# Quest.net
KiCad netlist of a schematic drawn in EAGLE
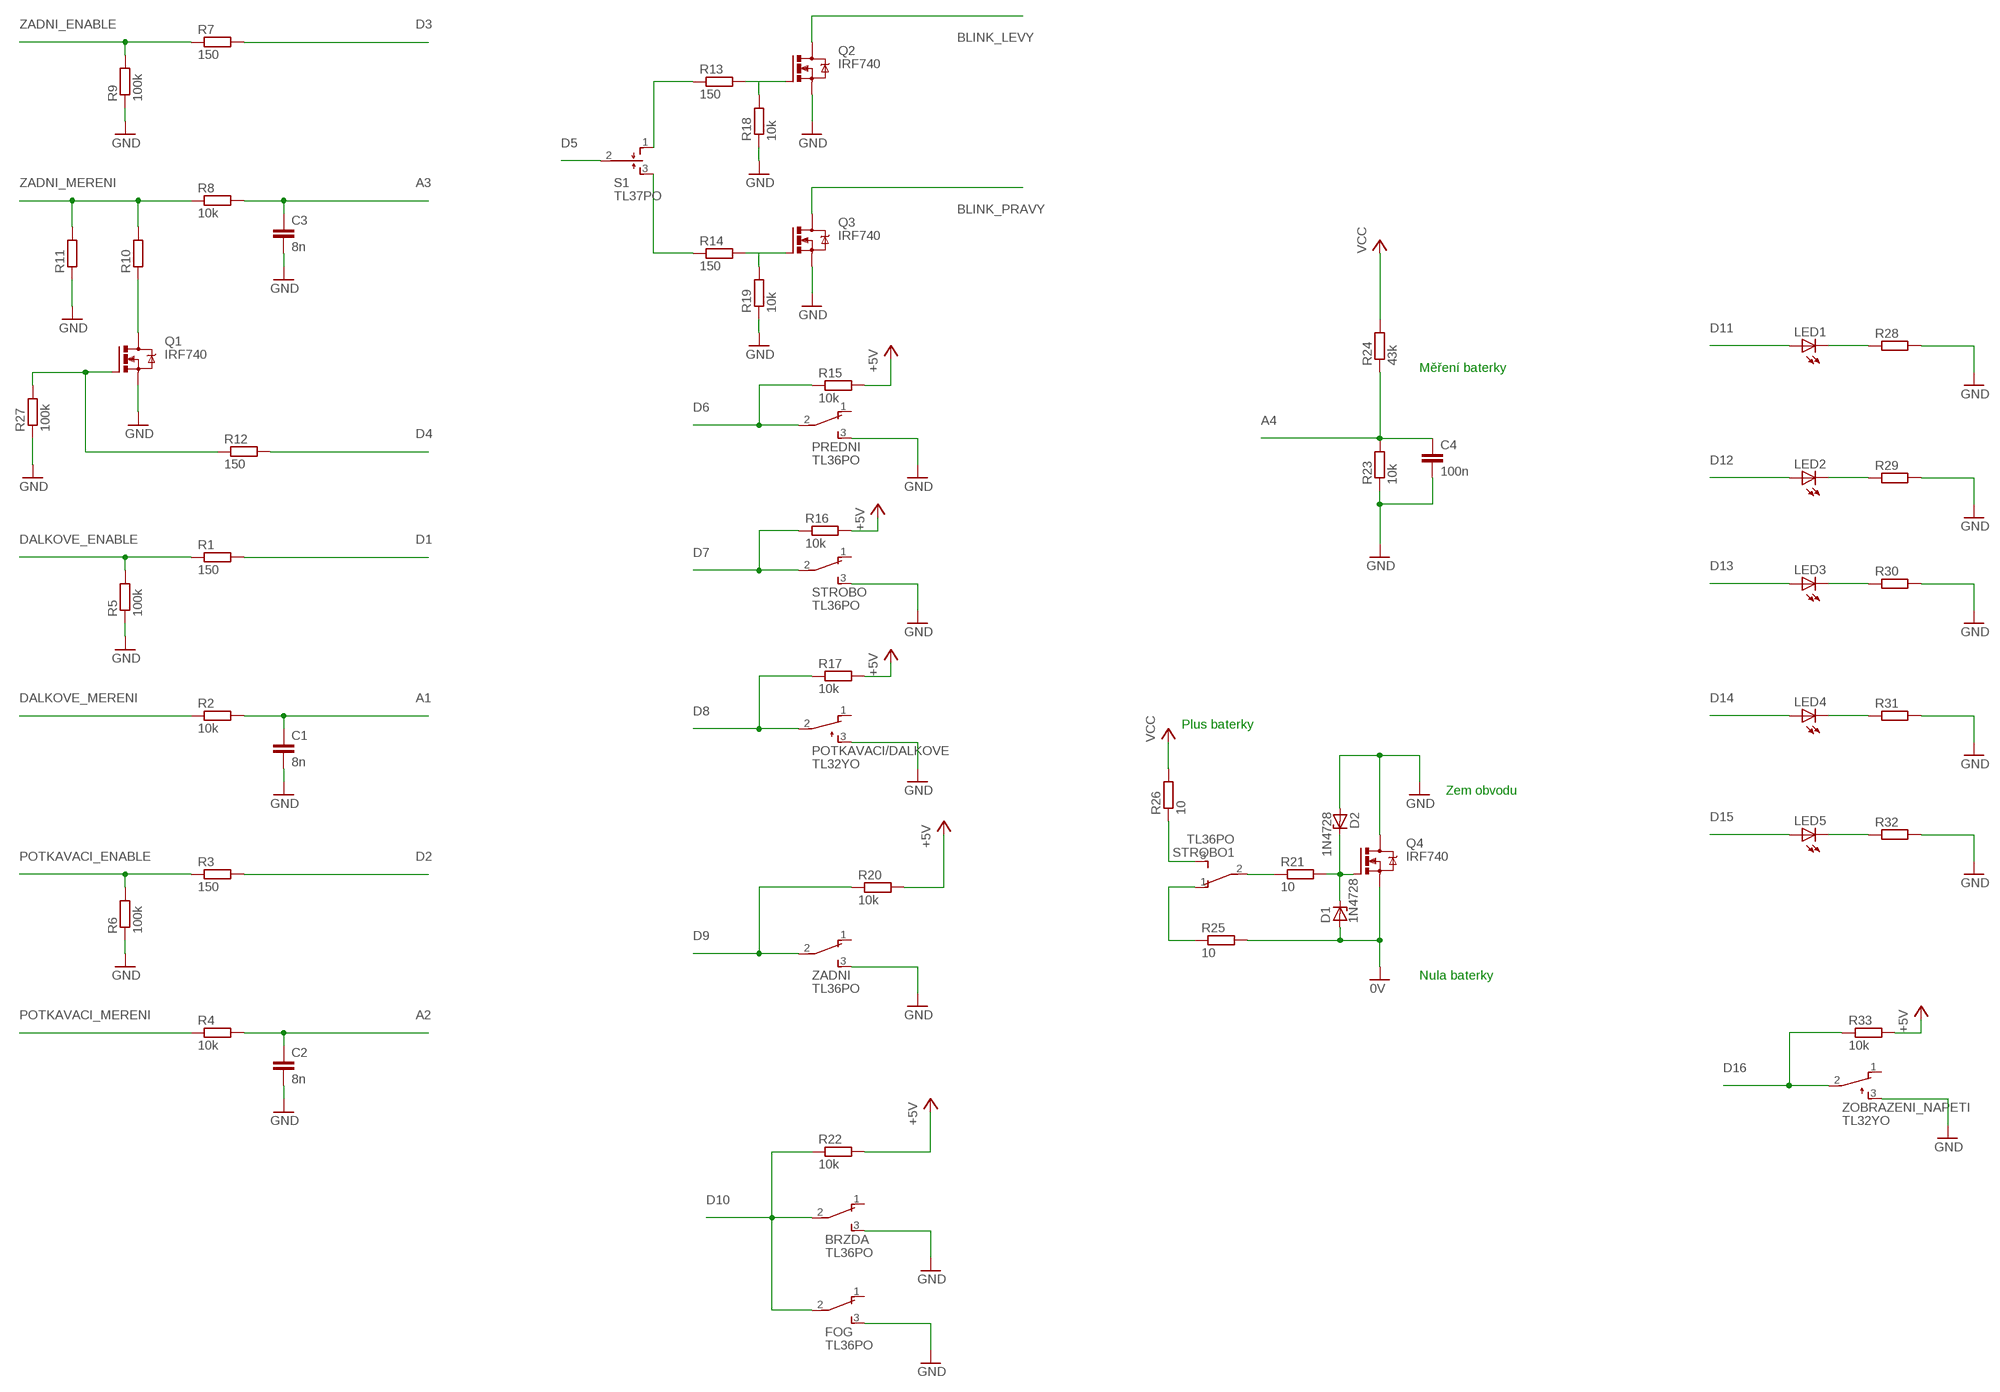
[diagram p0: schematic, sheet 1]

(export (version "E")
  (design (tool "Eeschema 10.0.6"))
  (components
    (comp (ref "BRZDA")
      (value "TL36PO")
      (footprint "eagle-import:TL3XPO")
      (libsource (lib "eagle-import") (part "TL36PO"))
    )
    (comp (ref "C1")
      (value "8n")
      (footprint "eagle-import:C050-024X044")
      (libsource (lib "eagle-import") (part "C-EU050-024X044"))
    )
    (comp (ref "C2")
      (value "8n")
      (footprint "eagle-import:C050-024X044")
      (libsource (lib "eagle-import") (part "C-EU050-024X044"))
    )
    (comp (ref "C3")
      (value "8n")
      (footprint "eagle-import:C050-024X044")
      (libsource (lib "eagle-import") (part "C-EU050-024X044"))
    )
    (comp (ref "C4")
      (value "100n")
      (footprint "eagle-import:C050-024X044")
      (libsource (lib "eagle-import") (part "C-EU050-024X044"))
    )
    (comp (ref "D1")
      (value "1N4728")
      (footprint "eagle-import:DO41Z10")
      (libsource (lib "eagle-import") (part "1N4728"))
    )
    (comp (ref "D2")
      (value "1N4728")
      (footprint "eagle-import:DO41Z10")
      (libsource (lib "eagle-import") (part "1N4728"))
    )
    (comp (ref "FOG")
      (value "TL36PO")
      (footprint "eagle-import:TL3XPO")
      (libsource (lib "eagle-import") (part "TL36PO"))
    )
    (comp (ref "LED1")
      (value "LED5MM")
      (footprint "eagle-import:LED5MM")
      (libsource (lib "eagle-import") (part "LED5MM"))
    )
    (comp (ref "LED2")
      (value "LED5MM")
      (footprint "eagle-import:LED5MM")
      (libsource (lib "eagle-import") (part "LED5MM"))
    )
    (comp (ref "LED3")
      (value "LED5MM")
      (footprint "eagle-import:LED5MM")
      (libsource (lib "eagle-import") (part "LED5MM"))
    )
    (comp (ref "LED4")
      (value "LED5MM")
      (footprint "eagle-import:LED5MM")
      (libsource (lib "eagle-import") (part "LED5MM"))
    )
    (comp (ref "LED5")
      (value "LED5MM")
      (footprint "eagle-import:LED5MM")
      (libsource (lib "eagle-import") (part "LED5MM"))
    )
    (comp (ref "POTKAVACI/DALKOVE")
      (value "TL32YO")
      (footprint "eagle-import:TL3XYO")
      (libsource (lib "eagle-import") (part "TL32YO"))
    )
    (comp (ref "PREDNI")
      (value "TL36PO")
      (footprint "eagle-import:TL3XPO")
      (libsource (lib "eagle-import") (part "TL36PO"))
    )
    (comp (ref "Q1")
      (value "IRF740")
      (footprint "eagle-import:TO220BV")
      (libsource (lib "eagle-import") (part "IRF740"))
    )
    (comp (ref "Q2")
      (value "IRF740")
      (footprint "eagle-import:TO220BV")
      (libsource (lib "eagle-import") (part "IRF740"))
    )
    (comp (ref "Q3")
      (value "IRF740")
      (footprint "eagle-import:TO220BV")
      (libsource (lib "eagle-import") (part "IRF740"))
    )
    (comp (ref "Q4")
      (value "IRF740")
      (footprint "eagle-import:TO220BV")
      (libsource (lib "eagle-import") (part "IRF740"))
    )
    (comp (ref "R1")
      (value "150")
      (footprint "eagle-import:0309_10")
      (libsource (lib "eagle-import") (part "R-EU_0309/10"))
    )
    (comp (ref "R2")
      (value "10k")
      (footprint "eagle-import:0309_10")
      (libsource (lib "eagle-import") (part "R-EU_0309/10"))
    )
    (comp (ref "R3")
      (value "150")
      (footprint "eagle-import:0309_10")
      (libsource (lib "eagle-import") (part "R-EU_0309/10"))
    )
    (comp (ref "R4")
      (value "10k")
      (footprint "eagle-import:0309_10")
      (libsource (lib "eagle-import") (part "R-EU_0309/10"))
    )
    (comp (ref "R5")
      (value "100k")
      (footprint "eagle-import:0309_10")
      (libsource (lib "eagle-import") (part "R-EU_0309/10"))
    )
    (comp (ref "R6")
      (value "100k")
      (footprint "eagle-import:0309_10")
      (libsource (lib "eagle-import") (part "R-EU_0309/10"))
    )
    (comp (ref "R7")
      (value "150")
      (footprint "eagle-import:0309_10")
      (libsource (lib "eagle-import") (part "R-EU_0309/10"))
    )
    (comp (ref "R8")
      (value "10k")
      (footprint "eagle-import:0309_10")
      (libsource (lib "eagle-import") (part "R-EU_0309/10"))
    )
    (comp (ref "R9")
      (value "100k")
      (footprint "eagle-import:0309_10")
      (libsource (lib "eagle-import") (part "R-EU_0309/10"))
    )
    (comp (ref "R10")
      (value "R-EU_0309/10")
      (footprint "eagle-import:0309_10")
      (libsource (lib "eagle-import") (part "R-EU_0309/10"))
    )
    (comp (ref "R11")
      (value "R-EU_0309/10")
      (footprint "eagle-import:0309_10")
      (libsource (lib "eagle-import") (part "R-EU_0309/10"))
    )
    (comp (ref "R12")
      (value "150")
      (footprint "eagle-import:0309_10")
      (libsource (lib "eagle-import") (part "R-EU_0309/10"))
    )
    (comp (ref "R13")
      (value "150")
      (footprint "eagle-import:0309_10")
      (libsource (lib "eagle-import") (part "R-EU_0309/10"))
    )
    (comp (ref "R14")
      (value "150")
      (footprint "eagle-import:0309_10")
      (libsource (lib "eagle-import") (part "R-EU_0309/10"))
    )
    (comp (ref "R15")
      (value "10k")
      (footprint "eagle-import:0309_10")
      (libsource (lib "eagle-import") (part "R-EU_0309/10"))
    )
    (comp (ref "R16")
      (value "10k")
      (footprint "eagle-import:0309_10")
      (libsource (lib "eagle-import") (part "R-EU_0309/10"))
    )
    (comp (ref "R17")
      (value "10k")
      (footprint "eagle-import:0309_10")
      (libsource (lib "eagle-import") (part "R-EU_0309/10"))
    )
    (comp (ref "R18")
      (value "10k")
      (footprint "eagle-import:0309_10")
      (libsource (lib "eagle-import") (part "R-EU_0309/10"))
    )
    (comp (ref "R19")
      (value "10k")
      (footprint "eagle-import:0309_10")
      (libsource (lib "eagle-import") (part "R-EU_0309/10"))
    )
    (comp (ref "R20")
      (value "10k")
      (footprint "eagle-import:0309_10")
      (libsource (lib "eagle-import") (part "R-EU_0309/10"))
    )
    (comp (ref "R21")
      (value "10")
      (footprint "eagle-import:0309_10")
      (libsource (lib "eagle-import") (part "R-EU_0309/10"))
    )
    (comp (ref "R22")
      (value "10k")
      (footprint "eagle-import:0309_10")
      (libsource (lib "eagle-import") (part "R-EU_0309/10"))
    )
    (comp (ref "R23")
      (value "10k")
      (footprint "eagle-import:0309_10")
      (libsource (lib "eagle-import") (part "R-EU_0309/10"))
    )
    (comp (ref "R24")
      (value "43k")
      (footprint "eagle-import:0309_10")
      (libsource (lib "eagle-import") (part "R-EU_0309/10"))
    )
    (comp (ref "R25")
      (value "10")
      (footprint "eagle-import:0309_10")
      (libsource (lib "eagle-import") (part "R-EU_0309/10"))
    )
    (comp (ref "R26")
      (value "10")
      (footprint "eagle-import:0309_10")
      (libsource (lib "eagle-import") (part "R-EU_0309/10"))
    )
    (comp (ref "R27")
      (value "100k")
      (footprint "eagle-import:0309_10")
      (libsource (lib "eagle-import") (part "R-EU_0309/10"))
    )
    (comp (ref "R28")
      (value "R-EU_0309/10")
      (footprint "eagle-import:0309_10")
      (libsource (lib "eagle-import") (part "R-EU_0309/10"))
    )
    (comp (ref "R29")
      (value "R-EU_0309/10")
      (footprint "eagle-import:0309_10")
      (libsource (lib "eagle-import") (part "R-EU_0309/10"))
    )
    (comp (ref "R30")
      (value "R-EU_0309/10")
      (footprint "eagle-import:0309_10")
      (libsource (lib "eagle-import") (part "R-EU_0309/10"))
    )
    (comp (ref "R31")
      (value "R-EU_0309/10")
      (footprint "eagle-import:0309_10")
      (libsource (lib "eagle-import") (part "R-EU_0309/10"))
    )
    (comp (ref "R32")
      (value "R-EU_0309/10")
      (footprint "eagle-import:0309_10")
      (libsource (lib "eagle-import") (part "R-EU_0309/10"))
    )
    (comp (ref "R33")
      (value "10k")
      (footprint "eagle-import:0309_10")
      (libsource (lib "eagle-import") (part "R-EU_0309/10"))
    )
    (comp (ref "S1")
      (value "TL37PO")
      (footprint "eagle-import:TL3XPO")
      (libsource (lib "eagle-import") (part "TL37PO"))
    )
    (comp (ref "STROBO")
      (value "TL36PO")
      (footprint "eagle-import:TL3XPO")
      (libsource (lib "eagle-import") (part "TL36PO"))
    )
    (comp (ref "STROBO1")
      (value "TL36PO")
      (footprint "eagle-import:TL3XPO")
      (libsource (lib "eagle-import") (part "TL36PO"))
    )
    (comp (ref "ZADNI")
      (value "TL36PO")
      (footprint "eagle-import:TL3XPO")
      (libsource (lib "eagle-import") (part "TL36PO"))
    )
    (comp (ref "ZOBRAZENI_NAPETI")
      (value "TL32YO")
      (footprint "eagle-import:TL3XYO")
      (libsource (lib "eagle-import") (part "TL32YO"))
    )
  )
  (nets
    (net (code "1") (name "+5V") (class "Default")
      (node (ref "R15") (pin "2") (pinfunction "2_2") (pintype "passive"))
      (node (ref "R16") (pin "2") (pinfunction "2_2") (pintype "passive"))
      (node (ref "R17") (pin "2") (pinfunction "2_2") (pintype "passive"))
      (node (ref "R20") (pin "2") (pinfunction "2_2") (pintype "passive"))
      (node (ref "R22") (pin "2") (pinfunction "2_2") (pintype "passive"))
      (node (ref "R33") (pin "2") (pinfunction "2_2") (pintype "passive"))
    )
    (net (code "2") (name "/A1") (class "Default")
      (node (ref "C1") (pin "1") (pinfunction "1_1") (pintype "passive"))
      (node (ref "R2") (pin "2") (pinfunction "2_2") (pintype "passive"))
    )
    (net (code "3") (name "/A2") (class "Default")
      (node (ref "C2") (pin "1") (pinfunction "1_1") (pintype "passive"))
      (node (ref "R4") (pin "2") (pinfunction "2_2") (pintype "passive"))
    )
    (net (code "4") (name "/A3") (class "Default")
      (node (ref "C3") (pin "1") (pinfunction "1_1") (pintype "passive"))
      (node (ref "R8") (pin "2") (pinfunction "2_2") (pintype "passive"))
    )
    (net (code "5") (name "/A4") (class "Default")
      (node (ref "C4") (pin "1") (pinfunction "1_1") (pintype "passive"))
      (node (ref "R23") (pin "2") (pinfunction "2_2") (pintype "passive"))
      (node (ref "R24") (pin "1") (pinfunction "1_1") (pintype "passive"))
    )
    (net (code "6") (name "/BLINK_LEVY") (class "Default")
      (node (ref "Q2") (pin "D") (pinfunction "D_D") (pintype "passive"))
    )
    (net (code "7") (name "/BLINK_PRAVY") (class "Default")
      (node (ref "Q3") (pin "D") (pinfunction "D_D") (pintype "passive"))
    )
    (net (code "8") (name "/D1") (class "Default")
      (node (ref "R1") (pin "2") (pinfunction "2_2") (pintype "passive"))
    )
    (net (code "9") (name "/D2") (class "Default")
      (node (ref "R3") (pin "2") (pinfunction "2_2") (pintype "passive"))
    )
    (net (code "10") (name "/D3") (class "Default")
      (node (ref "R7") (pin "2") (pinfunction "2_2") (pintype "passive"))
    )
    (net (code "11") (name "/D4") (class "Default")
      (node (ref "R12") (pin "2") (pinfunction "2_2") (pintype "passive"))
    )
    (net (code "12") (name "/D5") (class "Default")
      (node (ref "S1") (pin "2") (pinfunction "P_2") (pintype "passive"))
    )
    (net (code "13") (name "/D6") (class "Default")
      (node (ref "PREDNI") (pin "2") (pinfunction "P_2") (pintype "passive"))
      (node (ref "R15") (pin "1") (pinfunction "1_1") (pintype "passive"))
    )
    (net (code "14") (name "/D7") (class "Default")
      (node (ref "R16") (pin "1") (pinfunction "1_1") (pintype "passive"))
      (node (ref "STROBO") (pin "2") (pinfunction "P_2") (pintype "passive"))
    )
    (net (code "15") (name "/D8") (class "Default")
      (node (ref "POTKAVACI/DALKOVE") (pin "2") (pinfunction "P_2") (pintype "passive"))
      (node (ref "R17") (pin "1") (pinfunction "1_1") (pintype "passive"))
    )
    (net (code "16") (name "/D9") (class "Default")
      (node (ref "R20") (pin "1") (pinfunction "1_1") (pintype "passive"))
      (node (ref "ZADNI") (pin "2") (pinfunction "P_2") (pintype "passive"))
    )
    (net (code "17") (name "/D10") (class "Default")
      (node (ref "BRZDA") (pin "2") (pinfunction "P_2") (pintype "passive"))
      (node (ref "FOG") (pin "2") (pinfunction "P_2") (pintype "passive"))
      (node (ref "R22") (pin "1") (pinfunction "1_1") (pintype "passive"))
    )
    (net (code "18") (name "/D11") (class "Default")
      (node (ref "LED1") (pin "A") (pinfunction "A_A") (pintype "passive"))
    )
    (net (code "19") (name "/D12") (class "Default")
      (node (ref "LED2") (pin "A") (pinfunction "A_A") (pintype "passive"))
    )
    (net (code "20") (name "/D13") (class "Default")
      (node (ref "LED3") (pin "A") (pinfunction "A_A") (pintype "passive"))
    )
    (net (code "21") (name "/D14") (class "Default")
      (node (ref "LED4") (pin "A") (pinfunction "A_A") (pintype "passive"))
    )
    (net (code "22") (name "/D15") (class "Default")
      (node (ref "LED5") (pin "A") (pinfunction "A_A") (pintype "passive"))
    )
    (net (code "23") (name "/D16") (class "Default")
      (node (ref "R33") (pin "1") (pinfunction "1_1") (pintype "passive"))
      (node (ref "ZOBRAZENI_NAPETI") (pin "2") (pinfunction "P_2") (pintype "passive"))
    )
    (net (code "24") (name "/DALKOVE_ENABLE") (class "Default")
      (node (ref "R1") (pin "1") (pinfunction "1_1") (pintype "passive"))
      (node (ref "R5") (pin "2") (pinfunction "2_2") (pintype "passive"))
    )
    (net (code "25") (name "/DALKOVE_MERENI") (class "Default")
      (node (ref "R2") (pin "1") (pinfunction "1_1") (pintype "passive"))
    )
    (net (code "26") (name "/POTKAVACI_ENABLE") (class "Default")
      (node (ref "R3") (pin "1") (pinfunction "1_1") (pintype "passive"))
      (node (ref "R6") (pin "2") (pinfunction "2_2") (pintype "passive"))
    )
    (net (code "27") (name "/POTKAVACI_MERENI") (class "Default")
      (node (ref "R4") (pin "1") (pinfunction "1_1") (pintype "passive"))
    )
    (net (code "28") (name "/ZADNI_ENABLE") (class "Default")
      (node (ref "R7") (pin "1") (pinfunction "1_1") (pintype "passive"))
      (node (ref "R9") (pin "2") (pinfunction "2_2") (pintype "passive"))
    )
    (net (code "29") (name "/ZADNI_MERENI") (class "Default")
      (node (ref "R10") (pin "2") (pinfunction "2_2") (pintype "passive"))
      (node (ref "R11") (pin "2") (pinfunction "2_2") (pintype "passive"))
      (node (ref "R8") (pin "1") (pinfunction "1_1") (pintype "passive"))
    )
    (net (code "30") (name "0V") (class "Default")
      (node (ref "D1") (pin "A") (pinfunction "A_A") (pintype "passive"))
      (node (ref "Q4") (pin "S") (pinfunction "S_S") (pintype "passive"))
      (node (ref "R25") (pin "2") (pinfunction "2_2") (pintype "passive"))
    )
    (net (code "31") (name "GND") (class "Default")
      (node (ref "BRZDA") (pin "3") (pinfunction "S_3") (pintype "passive"))
      (node (ref "C1") (pin "2") (pinfunction "2_2") (pintype "passive"))
      (node (ref "C2") (pin "2") (pinfunction "2_2") (pintype "passive"))
      (node (ref "C3") (pin "2") (pinfunction "2_2") (pintype "passive"))
      (node (ref "C4") (pin "2") (pinfunction "2_2") (pintype "passive"))
      (node (ref "D2") (pin "A") (pinfunction "A_A") (pintype "passive"))
      (node (ref "FOG") (pin "3") (pinfunction "S_3") (pintype "passive"))
      (node (ref "POTKAVACI/DALKOVE") (pin "3") (pinfunction "S_3") (pintype "passive"))
      (node (ref "PREDNI") (pin "3") (pinfunction "S_3") (pintype "passive"))
      (node (ref "Q1") (pin "S") (pinfunction "S_S") (pintype "passive"))
      (node (ref "Q2") (pin "S") (pinfunction "S_S") (pintype "passive"))
      (node (ref "Q3") (pin "S") (pinfunction "S_S") (pintype "passive"))
      (node (ref "Q4") (pin "D") (pinfunction "D_D") (pintype "passive"))
      (node (ref "R11") (pin "1") (pinfunction "1_1") (pintype "passive"))
      (node (ref "R18") (pin "1") (pinfunction "1_1") (pintype "passive"))
      (node (ref "R19") (pin "1") (pinfunction "1_1") (pintype "passive"))
      (node (ref "R23") (pin "1") (pinfunction "1_1") (pintype "passive"))
      (node (ref "R27") (pin "1") (pinfunction "1_1") (pintype "passive"))
      (node (ref "R28") (pin "2") (pinfunction "2_2") (pintype "passive"))
      (node (ref "R29") (pin "2") (pinfunction "2_2") (pintype "passive"))
      (node (ref "R30") (pin "2") (pinfunction "2_2") (pintype "passive"))
      (node (ref "R31") (pin "2") (pinfunction "2_2") (pintype "passive"))
      (node (ref "R32") (pin "2") (pinfunction "2_2") (pintype "passive"))
      (node (ref "R5") (pin "1") (pinfunction "1_1") (pintype "passive"))
      (node (ref "R6") (pin "1") (pinfunction "1_1") (pintype "passive"))
      (node (ref "R9") (pin "1") (pinfunction "1_1") (pintype "passive"))
      (node (ref "STROBO") (pin "3") (pinfunction "S_3") (pintype "passive"))
      (node (ref "ZADNI") (pin "3") (pinfunction "S_3") (pintype "passive"))
      (node (ref "ZOBRAZENI_NAPETI") (pin "3") (pinfunction "S_3") (pintype "passive"))
    )
    (net (code "32") (name "Net-(D1-PadC)") (class "Default")
      (node (ref "D1") (pin "C") (pinfunction "C_C") (pintype "passive"))
      (node (ref "D2") (pin "C") (pinfunction "C_C") (pintype "passive"))
      (node (ref "Q4") (pin "G") (pinfunction "G_G") (pintype "passive"))
      (node (ref "R21") (pin "2") (pinfunction "2_2") (pintype "passive"))
    )
    (net (code "33") (name "Net-(LED1-C)") (class "Default")
      (node (ref "LED1") (pin "K") (pinfunction "C_K") (pintype "passive"))
      (node (ref "R28") (pin "1") (pinfunction "1_1") (pintype "passive"))
    )
    (net (code "34") (name "Net-(LED2-C)") (class "Default")
      (node (ref "LED2") (pin "K") (pinfunction "C_K") (pintype "passive"))
      (node (ref "R29") (pin "1") (pinfunction "1_1") (pintype "passive"))
    )
    (net (code "35") (name "Net-(LED3-C)") (class "Default")
      (node (ref "LED3") (pin "K") (pinfunction "C_K") (pintype "passive"))
      (node (ref "R30") (pin "1") (pinfunction "1_1") (pintype "passive"))
    )
    (net (code "36") (name "Net-(LED4-C)") (class "Default")
      (node (ref "LED4") (pin "K") (pinfunction "C_K") (pintype "passive"))
      (node (ref "R31") (pin "1") (pinfunction "1_1") (pintype "passive"))
    )
    (net (code "37") (name "Net-(LED5-C)") (class "Default")
      (node (ref "LED5") (pin "K") (pinfunction "C_K") (pintype "passive"))
      (node (ref "R32") (pin "1") (pinfunction "1_1") (pintype "passive"))
    )
    (net (code "38") (name "Net-(Q1-PadD)") (class "Default")
      (node (ref "Q1") (pin "D") (pinfunction "D_D") (pintype "passive"))
      (node (ref "R10") (pin "1") (pinfunction "1_1") (pintype "passive"))
    )
    (net (code "39") (name "Net-(Q1-PadG)") (class "Default")
      (node (ref "Q1") (pin "G") (pinfunction "G_G") (pintype "passive"))
      (node (ref "R12") (pin "1") (pinfunction "1_1") (pintype "passive"))
      (node (ref "R27") (pin "2") (pinfunction "2_2") (pintype "passive"))
    )
    (net (code "40") (name "Net-(Q2-PadG)") (class "Default")
      (node (ref "Q2") (pin "G") (pinfunction "G_G") (pintype "passive"))
      (node (ref "R13") (pin "2") (pinfunction "2_2") (pintype "passive"))
      (node (ref "R18") (pin "2") (pinfunction "2_2") (pintype "passive"))
    )
    (net (code "41") (name "Net-(Q3-PadG)") (class "Default")
      (node (ref "Q3") (pin "G") (pinfunction "G_G") (pintype "passive"))
      (node (ref "R14") (pin "2") (pinfunction "2_2") (pintype "passive"))
      (node (ref "R19") (pin "2") (pinfunction "2_2") (pintype "passive"))
    )
    (net (code "42") (name "Net-(S1-O)") (class "Default")
      (node (ref "R13") (pin "1") (pinfunction "1_1") (pintype "passive"))
      (node (ref "S1") (pin "1") (pinfunction "O_1") (pintype "passive"))
    )
    (net (code "43") (name "Net-(S1-S)") (class "Default")
      (node (ref "R14") (pin "1") (pinfunction "1_1") (pintype "passive"))
      (node (ref "S1") (pin "3") (pinfunction "S_3") (pintype "passive"))
    )
    (net (code "44") (name "Net-(STROBO1-O)") (class "Default")
      (node (ref "R25") (pin "1") (pinfunction "1_1") (pintype "passive"))
      (node (ref "STROBO1") (pin "1") (pinfunction "O_1") (pintype "passive"))
    )
    (net (code "45") (name "Net-(STROBO1-P)") (class "Default")
      (node (ref "R21") (pin "1") (pinfunction "1_1") (pintype "passive"))
      (node (ref "STROBO1") (pin "2") (pinfunction "P_2") (pintype "passive"))
    )
    (net (code "46") (name "Net-(STROBO1-S)") (class "Default")
      (node (ref "R26") (pin "1") (pinfunction "1_1") (pintype "passive"))
      (node (ref "STROBO1") (pin "3") (pinfunction "S_3") (pintype "passive"))
    )
    (net (code "47") (name "VCC") (class "Default")
      (node (ref "R24") (pin "2") (pinfunction "2_2") (pintype "passive"))
      (node (ref "R26") (pin "2") (pinfunction "2_2") (pintype "passive"))
    )
    (net (code "48") (name "unconnected-(BRZDA-O-Pad1)") (class "Default")
      (node (ref "BRZDA") (pin "1") (pinfunction "O_1") (pintype "passive"))
    )
    (net (code "49") (name "unconnected-(FOG-O-Pad1)") (class "Default")
      (node (ref "FOG") (pin "1") (pinfunction "O_1") (pintype "passive"))
    )
    (net (code "50") (name "unconnected-(POTKAVACI/DALKOVE-O-Pad1)") (class "Default")
      (node (ref "POTKAVACI/DALKOVE") (pin "1") (pinfunction "O_1") (pintype "passive"))
    )
    (net (code "51") (name "unconnected-(PREDNI-O-Pad1)") (class "Default")
      (node (ref "PREDNI") (pin "1") (pinfunction "O_1") (pintype "passive"))
    )
    (net (code "52") (name "unconnected-(STROBO-O-Pad1)") (class "Default")
      (node (ref "STROBO") (pin "1") (pinfunction "O_1") (pintype "passive"))
    )
    (net (code "53") (name "unconnected-(ZADNI-O-Pad1)") (class "Default")
      (node (ref "ZADNI") (pin "1") (pinfunction "O_1") (pintype "passive"))
    )
    (net (code "54") (name "unconnected-(ZOBRAZENI_NAPETI-O-Pad1)") (class "Default")
      (node (ref "ZOBRAZENI_NAPETI") (pin "1") (pinfunction "O_1") (pintype "passive"))
    )
  )
)
